# main.net
KiCad netlist of a schematic drawn in Altium Designer
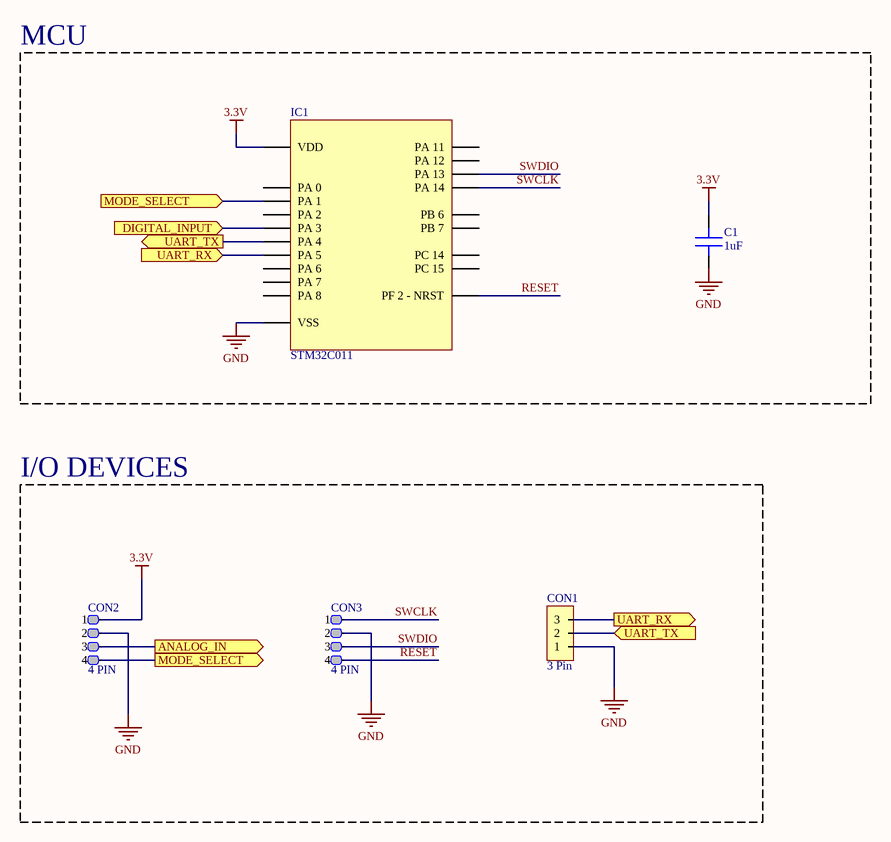
[diagram p0: main.SchDoc]

(export (version "E")
  (design (tool "Eeschema 10.0.6"))
  (components
    (comp (ref "C1")
      (value "1uF")
      (footprint "C 0603")
      (description "MLCC Capacitor")
      (libsource (lib "sigma-delta-adc-uart") (part "Capacitor"))
    )
    (comp (ref "CON1")
      (value "3 Pin")
      (footprint "Goldpin 2.54 3P")
      (libsource (lib "Connectors") (part "3 Pin"))
    )
    (comp (ref "CON2")
      (value "4 PIN")
      (footprint "Goldpin 2.54 4P")
      (libsource (lib "Connectors") (part "4 PIN"))
    )
    (comp (ref "CON3")
      (value "4 PIN")
      (footprint "BM04B-SRSS-TB")
      (libsource (lib "Connectors") (part "4 PIN"))
    )
    (comp (ref "IC1")
      (value "STM32C011")
      (footprint "20-UFQFPN")
      (description "UFQFPN 20")
      (libsource (lib "Components") (part "STM32C011F4U"))
    )
  )
  (nets
    (net (code "1") (name "/ANALOG_IN") (class "Default")
      (node (ref "CON2") (pin "3") (pinfunction "3_3") (pintype "passive"))
    )
    (net (code "2") (name "/DIGITAL_INPUT") (class "Default")
      (node (ref "IC1") (pin "8") (pinfunction "PA_3_8") (pintype "passive"))
    )
    (net (code "3") (name "/MODE_SELECT") (class "Default")
      (node (ref "CON2") (pin "4") (pinfunction "4_4") (pintype "passive"))
      (node (ref "IC1") (pin "6") (pinfunction "PA_1_6") (pintype "passive"))
    )
    (net (code "4") (name "/RESET") (class "Default")
      (node (ref "CON3") (pin "4") (pinfunction "4_4") (pintype "passive"))
      (node (ref "IC1") (pin "4") (pinfunction "PF_2_-_NRST_4") (pintype "passive"))
    )
    (net (code "5") (name "/SWCLK") (class "Default")
      (node (ref "CON3") (pin "1") (pinfunction "1_1") (pintype "passive"))
      (node (ref "IC1") (pin "17") (pinfunction "PA_14_17") (pintype "passive"))
    )
    (net (code "6") (name "/SWDIO") (class "Default")
      (node (ref "CON3") (pin "3") (pinfunction "3_3") (pintype "passive"))
      (node (ref "IC1") (pin "16") (pinfunction "PA_13_16") (pintype "passive"))
    )
    (net (code "7") (name "/UART_RX") (class "Default")
      (node (ref "CON1") (pin "3") (pinfunction "3_3") (pintype "passive"))
      (node (ref "IC1") (pin "10") (pinfunction "PA_5_10") (pintype "passive"))
    )
    (net (code "8") (name "/UART_TX") (class "Default")
      (node (ref "CON1") (pin "2") (pinfunction "2_2") (pintype "passive"))
      (node (ref "IC1") (pin "9") (pinfunction "PA_4_9") (pintype "passive"))
    )
    (net (code "9") (name "3.3V") (class "Default")
      (node (ref "C1") (pin "1") (pinfunction "1_1") (pintype "passive"))
      (node (ref "CON2") (pin "1") (pinfunction "1_1") (pintype "passive"))
      (node (ref "IC1") (pin "2") (pinfunction "VDD_2") (pintype "passive"))
    )
    (net (code "10") (name "GND") (class "Default")
      (node (ref "C1") (pin "2") (pinfunction "2_2") (pintype "passive"))
      (node (ref "CON1") (pin "1") (pinfunction "1_1") (pintype "passive"))
      (node (ref "CON2") (pin "2") (pinfunction "2_2") (pintype "passive"))
      (node (ref "CON3") (pin "2") (pinfunction "2_2") (pintype "passive"))
      (node (ref "IC1") (pin "3") (pinfunction "VSS_3") (pintype "passive"))
    )
    (net (code "11") (name "unconnected-(IC1-PA_0-Pad5)") (class "Default")
      (node (ref "IC1") (pin "5") (pinfunction "PA_0_5") (pintype "passive"))
    )
    (net (code "12") (name "unconnected-(IC1-PA_2-Pad7)") (class "Default")
      (node (ref "IC1") (pin "7") (pinfunction "PA_2_7") (pintype "passive"))
    )
    (net (code "13") (name "unconnected-(IC1-PA_6-Pad11)") (class "Default")
      (node (ref "IC1") (pin "11") (pinfunction "PA_6_11") (pintype "passive"))
    )
    (net (code "14") (name "unconnected-(IC1-PA_7-Pad12)") (class "Default")
      (node (ref "IC1") (pin "12") (pinfunction "PA_7_12") (pintype "passive"))
    )
    (net (code "15") (name "unconnected-(IC1-PA_8-Pad13)") (class "Default")
      (node (ref "IC1") (pin "13") (pinfunction "PA_8_13") (pintype "passive"))
    )
    (net (code "16") (name "unconnected-(IC1-PA_11-Pad14)") (class "Default")
      (node (ref "IC1") (pin "14") (pinfunction "PA_11_14") (pintype "passive"))
    )
    (net (code "17") (name "unconnected-(IC1-PA_12-Pad15)") (class "Default")
      (node (ref "IC1") (pin "15") (pinfunction "PA_12_15") (pintype "passive"))
    )
    (net (code "18") (name "unconnected-(IC1-PB_6-Pad18)") (class "Default")
      (node (ref "IC1") (pin "18") (pinfunction "PB_6_18") (pintype "passive"))
    )
    (net (code "19") (name "unconnected-(IC1-PB_7-Pad19)") (class "Default")
      (node (ref "IC1") (pin "19") (pinfunction "PB_7_19") (pintype "passive"))
    )
    (net (code "20") (name "unconnected-(IC1-PC_14-Pad20)") (class "Default")
      (node (ref "IC1") (pin "20") (pinfunction "PC_14_20") (pintype "passive"))
    )
    (net (code "21") (name "unconnected-(IC1-PC_15-Pad1)") (class "Default")
      (node (ref "IC1") (pin "1") (pinfunction "PC_15_1") (pintype "passive"))
    )
  )
)
